# FPGA_ADC.net
KiCad netlist of a schematic drawn in Altium Designer
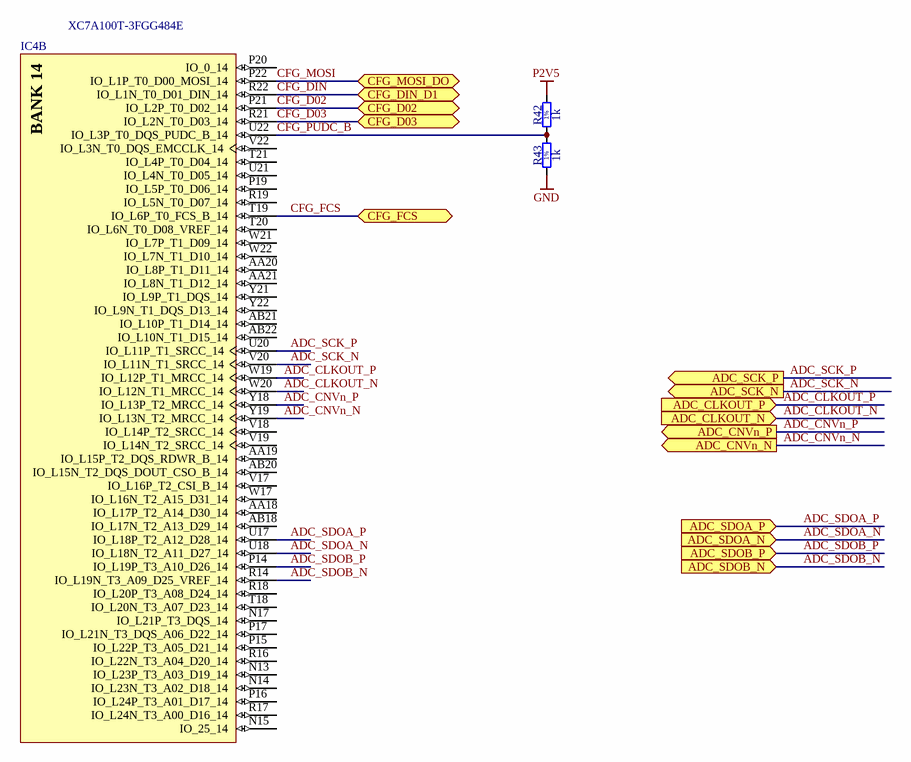
[diagram p0: FPGA_ADC.SchDoc]

(export (version "E")
  (design (tool "Eeschema 10.0.6"))
  (components
    (comp (ref "IC4")
      (value "XC7A100T-3FGG484E")
      (footprint "FGG484")
      (description "Artix-7 FPGA, 285 User I/Os, 4 GTP, 484-Ball BGA, Speed Grade 3, Extended Grade, Pb-Free")
      (fields (field (name "GENERIC PART NUMBER") "XC7A100T") (field (name "MANUFACTURER") "Xilinx"))
      (libsource (lib "Altium Content Vault") (part "XC7A100T-3FGG484E"))
    )
    (comp (ref "R42")
      (value "1k")
      (footprint "RESC1005X40N")
      (description "Resistor - 1%")
      (fields
        (field (name "PART NUMBER") "R0402_1K_1%_0.0625W_100PPM")
        (field (name "POWER") "0.0625W")
        (field (name "AUTHOR") "CERN DEM JLC")
      )
      (libsource (lib "Resistors") (part "Resistor - 1%"))
    )
    (comp (ref "R43")
      (value "1k")
      (footprint "RESC1005X40N")
      (description "Resistor - 1%")
      (fields
        (field (name "PART NUMBER") "R0402_1K_1%_0.0625W_100PPM")
        (field (name "POWER") "0.0625W")
        (field (name "AUTHOR") "CERN DEM JLC")
      )
      (libsource (lib "Resistors") (part "Resistor - 1%"))
    )
  )
  (nets
    (net (code "1") (name "/ADC_CLKOUT_N") (class "Default")
      (node (ref "IC4") (pin "W20") (pinfunction "IO_L12N_T1_MRCC_14_W20") (pintype "bidirectional"))
    )
    (net (code "2") (name "/ADC_CLKOUT_P") (class "Default")
      (node (ref "IC4") (pin "W19") (pinfunction "IO_L12P_T1_MRCC_14_W19") (pintype "bidirectional"))
    )
    (net (code "3") (name "/ADC_CNVn_N") (class "Default")
      (node (ref "IC4") (pin "Y19") (pinfunction "IO_L13N_T2_MRCC_14_Y19") (pintype "bidirectional"))
    )
    (net (code "4") (name "/ADC_CNVn_P") (class "Default")
      (node (ref "IC4") (pin "Y18") (pinfunction "IO_L13P_T2_MRCC_14_Y18") (pintype "bidirectional"))
    )
    (net (code "5") (name "/ADC_SCK_N") (class "Default")
      (node (ref "IC4") (pin "V20") (pinfunction "IO_L11N_T1_SRCC_14_V20") (pintype "bidirectional"))
    )
    (net (code "6") (name "/ADC_SCK_P") (class "Default")
      (node (ref "IC4") (pin "U20") (pinfunction "IO_L11P_T1_SRCC_14_U20") (pintype "bidirectional"))
    )
    (net (code "7") (name "/ADC_SDOA_N") (class "Default")
      (node (ref "IC4") (pin "U18") (pinfunction "IO_L18N_T2_A11_D27_14_U18") (pintype "bidirectional"))
    )
    (net (code "8") (name "/ADC_SDOA_P") (class "Default")
      (node (ref "IC4") (pin "U17") (pinfunction "IO_L18P_T2_A12_D28_14_U17") (pintype "bidirectional"))
    )
    (net (code "9") (name "/ADC_SDOB_N") (class "Default")
      (node (ref "IC4") (pin "R14") (pinfunction "IO_L19N_T3_A09_D25_VREF_14_R14") (pintype "bidirectional"))
    )
    (net (code "10") (name "/ADC_SDOB_P") (class "Default")
      (node (ref "IC4") (pin "P14") (pinfunction "IO_L19P_T3_A10_D26_14_P14") (pintype "bidirectional"))
    )
    (net (code "11") (name "/CFG_D02") (class "Default")
      (node (ref "IC4") (pin "P21") (pinfunction "IO_L2P_T0_D02_14_P21") (pintype "bidirectional"))
    )
    (net (code "12") (name "/CFG_D03") (class "Default")
      (node (ref "IC4") (pin "R21") (pinfunction "IO_L2N_T0_D03_14_R21") (pintype "bidirectional"))
    )
    (net (code "13") (name "/CFG_DIN") (class "Default")
      (node (ref "IC4") (pin "R22") (pinfunction "IO_L1N_T0_D01_DIN_14_R22") (pintype "bidirectional"))
    )
    (net (code "14") (name "/CFG_FCS") (class "Default")
      (node (ref "IC4") (pin "T19") (pinfunction "IO_L6P_T0_FCS_B_14_T19") (pintype "bidirectional"))
    )
    (net (code "15") (name "/CFG_MOSI") (class "Default")
      (node (ref "IC4") (pin "P22") (pinfunction "IO_L1P_T0_D00_MOSI_14_P22") (pintype "bidirectional"))
    )
    (net (code "16") (name "/CFG_PUDC_B") (class "Default")
      (node (ref "IC4") (pin "U22") (pinfunction "IO_L3P_T0_DQS_PUDC_B_14_U22") (pintype "bidirectional"))
      (node (ref "R42") (pin "1") (pinfunction "1_1") (pintype "passive"))
      (node (ref "R43") (pin "2") (pinfunction "2_2") (pintype "passive"))
    )
    (net (code "17") (name "GND") (class "Default")
      (node (ref "R43") (pin "1") (pinfunction "1_1") (pintype "passive"))
    )
    (net (code "18") (name "P2V5") (class "Default")
      (node (ref "R42") (pin "2") (pinfunction "2_2") (pintype "passive"))
    )
    (net (code "19") (name "unconnected-(IC4B-IO_0_14-PadP20)") (class "Default")
      (node (ref "IC4") (pin "P20") (pinfunction "IO_0_14_P20") (pintype "bidirectional"))
    )
    (net (code "20") (name "unconnected-(IC4B-IO_25_14-PadN15)") (class "Default")
      (node (ref "IC4") (pin "N15") (pinfunction "IO_25_14_N15") (pintype "bidirectional"))
    )
    (net (code "21") (name "unconnected-(IC4B-IO_L3N_T0_DQS_EMCCLK_14-PadV22)") (class "Default")
      (node (ref "IC4") (pin "V22") (pinfunction "IO_L3N_T0_DQS_EMCCLK_14_V22") (pintype "bidirectional"))
    )
    (net (code "22") (name "unconnected-(IC4B-IO_L4N_T0_D05_14-PadU21)") (class "Default")
      (node (ref "IC4") (pin "U21") (pinfunction "IO_L4N_T0_D05_14_U21") (pintype "bidirectional"))
    )
    (net (code "23") (name "unconnected-(IC4B-IO_L4P_T0_D04_14-PadT21)") (class "Default")
      (node (ref "IC4") (pin "T21") (pinfunction "IO_L4P_T0_D04_14_T21") (pintype "bidirectional"))
    )
    (net (code "24") (name "unconnected-(IC4B-IO_L5N_T0_D07_14-PadR19)") (class "Default")
      (node (ref "IC4") (pin "R19") (pinfunction "IO_L5N_T0_D07_14_R19") (pintype "bidirectional"))
    )
    (net (code "25") (name "unconnected-(IC4B-IO_L5P_T0_D06_14-PadP19)") (class "Default")
      (node (ref "IC4") (pin "P19") (pinfunction "IO_L5P_T0_D06_14_P19") (pintype "bidirectional"))
    )
    (net (code "26") (name "unconnected-(IC4B-IO_L6N_T0_D08_VREF_14-PadT20)") (class "Default")
      (node (ref "IC4") (pin "T20") (pinfunction "IO_L6N_T0_D08_VREF_14_T20") (pintype "bidirectional"))
    )
    (net (code "27") (name "unconnected-(IC4B-IO_L7N_T1_D10_14-PadW22)") (class "Default")
      (node (ref "IC4") (pin "W22") (pinfunction "IO_L7N_T1_D10_14_W22") (pintype "bidirectional"))
    )
    (net (code "28") (name "unconnected-(IC4B-IO_L7P_T1_D09_14-PadW21)") (class "Default")
      (node (ref "IC4") (pin "W21") (pinfunction "IO_L7P_T1_D09_14_W21") (pintype "bidirectional"))
    )
    (net (code "29") (name "unconnected-(IC4B-IO_L8N_T1_D12_14-PadAA21)") (class "Default")
      (node (ref "IC4") (pin "AA21") (pinfunction "IO_L8N_T1_D12_14_AA21") (pintype "bidirectional"))
    )
    (net (code "30") (name "unconnected-(IC4B-IO_L8P_T1_D11_14-PadAA20)") (class "Default")
      (node (ref "IC4") (pin "AA20") (pinfunction "IO_L8P_T1_D11_14_AA20") (pintype "bidirectional"))
    )
    (net (code "31") (name "unconnected-(IC4B-IO_L9N_T1_DQS_D13_14-PadY22)") (class "Default")
      (node (ref "IC4") (pin "Y22") (pinfunction "IO_L9N_T1_DQS_D13_14_Y22") (pintype "bidirectional"))
    )
    (net (code "32") (name "unconnected-(IC4B-IO_L9P_T1_DQS_14-PadY21)") (class "Default")
      (node (ref "IC4") (pin "Y21") (pinfunction "IO_L9P_T1_DQS_14_Y21") (pintype "bidirectional"))
    )
    (net (code "33") (name "unconnected-(IC4B-IO_L10N_T1_D15_14-PadAB22)") (class "Default")
      (node (ref "IC4") (pin "AB22") (pinfunction "IO_L10N_T1_D15_14_AB22") (pintype "bidirectional"))
    )
    (net (code "34") (name "unconnected-(IC4B-IO_L10P_T1_D14_14-PadAB21)") (class "Default")
      (node (ref "IC4") (pin "AB21") (pinfunction "IO_L10P_T1_D14_14_AB21") (pintype "bidirectional"))
    )
    (net (code "35") (name "unconnected-(IC4B-IO_L14N_T2_SRCC_14-PadV19)") (class "Default")
      (node (ref "IC4") (pin "V19") (pinfunction "IO_L14N_T2_SRCC_14_V19") (pintype "bidirectional"))
    )
    (net (code "36") (name "unconnected-(IC4B-IO_L14P_T2_SRCC_14-PadV18)") (class "Default")
      (node (ref "IC4") (pin "V18") (pinfunction "IO_L14P_T2_SRCC_14_V18") (pintype "bidirectional"))
    )
    (net (code "37") (name "unconnected-(IC4B-IO_L15N_T2_DQS_DOUT_CSO_B_14-PadAB20)") (class "Default")
      (node (ref "IC4") (pin "AB20") (pinfunction "IO_L15N_T2_DQS_DOUT_CSO_B_14_AB20") (pintype "bidirectional"))
    )
    (net (code "38") (name "unconnected-(IC4B-IO_L15P_T2_DQS_RDWR_B_14-PadAA19)") (class "Default")
      (node (ref "IC4") (pin "AA19") (pinfunction "IO_L15P_T2_DQS_RDWR_B_14_AA19") (pintype "bidirectional"))
    )
    (net (code "39") (name "unconnected-(IC4B-IO_L16N_T2_A15_D31_14-PadW17)") (class "Default")
      (node (ref "IC4") (pin "W17") (pinfunction "IO_L16N_T2_A15_D31_14_W17") (pintype "bidirectional"))
    )
    (net (code "40") (name "unconnected-(IC4B-IO_L16P_T2_CSI_B_14-PadV17)") (class "Default")
      (node (ref "IC4") (pin "V17") (pinfunction "IO_L16P_T2_CSI_B_14_V17") (pintype "bidirectional"))
    )
    (net (code "41") (name "unconnected-(IC4B-IO_L17N_T2_A13_D29_14-PadAB18)") (class "Default")
      (node (ref "IC4") (pin "AB18") (pinfunction "IO_L17N_T2_A13_D29_14_AB18") (pintype "bidirectional"))
    )
    (net (code "42") (name "unconnected-(IC4B-IO_L17P_T2_A14_D30_14-PadAA18)") (class "Default")
      (node (ref "IC4") (pin "AA18") (pinfunction "IO_L17P_T2_A14_D30_14_AA18") (pintype "bidirectional"))
    )
    (net (code "43") (name "unconnected-(IC4B-IO_L20N_T3_A07_D23_14-PadT18)") (class "Default")
      (node (ref "IC4") (pin "T18") (pinfunction "IO_L20N_T3_A07_D23_14_T18") (pintype "bidirectional"))
    )
    (net (code "44") (name "unconnected-(IC4B-IO_L20P_T3_A08_D24_14-PadR18)") (class "Default")
      (node (ref "IC4") (pin "R18") (pinfunction "IO_L20P_T3_A08_D24_14_R18") (pintype "bidirectional"))
    )
    (net (code "45") (name "unconnected-(IC4B-IO_L21N_T3_DQS_A06_D22_14-PadP17)") (class "Default")
      (node (ref "IC4") (pin "P17") (pinfunction "IO_L21N_T3_DQS_A06_D22_14_P17") (pintype "bidirectional"))
    )
    (net (code "46") (name "unconnected-(IC4B-IO_L21P_T3_DQS_14-PadN17)") (class "Default")
      (node (ref "IC4") (pin "N17") (pinfunction "IO_L21P_T3_DQS_14_N17") (pintype "bidirectional"))
    )
    (net (code "47") (name "unconnected-(IC4B-IO_L22N_T3_A04_D20_14-PadR16)") (class "Default")
      (node (ref "IC4") (pin "R16") (pinfunction "IO_L22N_T3_A04_D20_14_R16") (pintype "bidirectional"))
    )
    (net (code "48") (name "unconnected-(IC4B-IO_L22P_T3_A05_D21_14-PadP15)") (class "Default")
      (node (ref "IC4") (pin "P15") (pinfunction "IO_L22P_T3_A05_D21_14_P15") (pintype "bidirectional"))
    )
    (net (code "49") (name "unconnected-(IC4B-IO_L23N_T3_A02_D18_14-PadN14)") (class "Default")
      (node (ref "IC4") (pin "N14") (pinfunction "IO_L23N_T3_A02_D18_14_N14") (pintype "bidirectional"))
    )
    (net (code "50") (name "unconnected-(IC4B-IO_L23P_T3_A03_D19_14-PadN13)") (class "Default")
      (node (ref "IC4") (pin "N13") (pinfunction "IO_L23P_T3_A03_D19_14_N13") (pintype "bidirectional"))
    )
    (net (code "51") (name "unconnected-(IC4B-IO_L24N_T3_A00_D16_14-PadR17)") (class "Default")
      (node (ref "IC4") (pin "R17") (pinfunction "IO_L24N_T3_A00_D16_14_R17") (pintype "bidirectional"))
    )
    (net (code "52") (name "unconnected-(IC4B-IO_L24P_T3_A01_D17_14-PadP16)") (class "Default")
      (node (ref "IC4") (pin "P16") (pinfunction "IO_L24P_T3_A01_D17_14_P16") (pintype "bidirectional"))
    )
  )
)
